# PCB_Design.net
KiCad netlist of a schematic drawn in Altium Designer
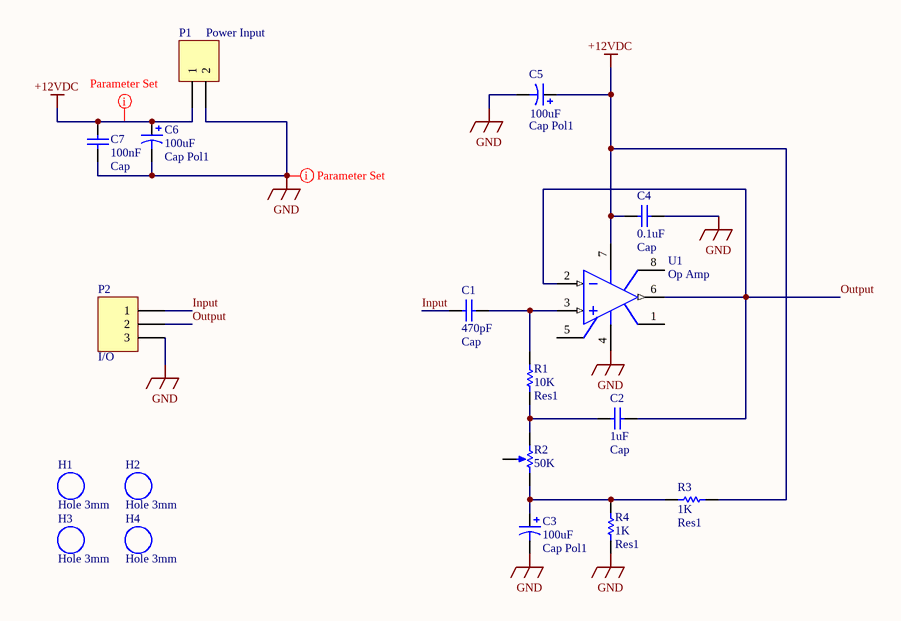
[diagram p0: PCB_Design.SchDoc]

(export (version "E")
  (design (tool "Eeschema 10.0.6"))
  (components
    (comp (ref "C1")
      (value "Cap")
      (footprint "RAD-0.3")
      (description "Capacitor")
      (fields (field (name "ALTIUM_VALUE") "470pF") (field (name "PUBLISHER") "Altium Limited"))
      (libsource (lib "Miscellaneous Devices") (part "Cap"))
    )
    (comp (ref "C2")
      (value "Cap")
      (footprint "RAD-0.3")
      (description "Capacitor")
      (fields (field (name "ALTIUM_VALUE") "1uF") (field (name "PUBLISHER") "Altium Limited"))
      (libsource (lib "Miscellaneous Devices") (part "Cap"))
    )
    (comp (ref "C3")
      (value "Cap Pol1")
      (footprint "RB7.6-15")
      (description "Polarized Capacitor (Radial)")
      (fields (field (name "ALTIUM_VALUE") "100uF") (field (name "PUBLISHER") "Altium Limited"))
      (libsource (lib "Miscellaneous Devices") (part "Cap Pol1"))
    )
    (comp (ref "C4")
      (value "Cap")
      (footprint "RAD-0.3")
      (description "Capacitor")
      (fields (field (name "ALTIUM_VALUE") "0.1uF") (field (name "PUBLISHER") "Altium Limited"))
      (libsource (lib "Miscellaneous Devices") (part "Cap"))
    )
    (comp (ref "C5")
      (value "Cap Pol1")
      (footprint "RB7.6-15")
      (description "Polarized Capacitor (Radial)")
      (fields (field (name "ALTIUM_VALUE") "100uF") (field (name "PUBLISHER") "Altium Limited"))
      (libsource (lib "Miscellaneous Devices") (part "Cap Pol1"))
    )
    (comp (ref "C6")
      (value "Cap Pol1")
      (footprint "RB7.6-15")
      (description "Polarized Capacitor (Radial)")
      (fields (field (name "ALTIUM_VALUE") "100uF") (field (name "PUBLISHER") "Altium Limited"))
      (libsource (lib "Miscellaneous Devices") (part "Cap Pol1"))
    )
    (comp (ref "C7")
      (value "Cap")
      (footprint "RAD-0.3")
      (description "Capacitor")
      (fields (field (name "ALTIUM_VALUE") "100nF") (field (name "PUBLISHER") "Altium Limited"))
      (libsource (lib "Miscellaneous Devices") (part "Cap"))
    )
    (comp (ref "H1")
      (value "Hole 3mm")
      (footprint "Hole 3mm")
      (libsource (lib "ECE Lib 22") (part "Hole 3mm"))
    )
    (comp (ref "H2")
      (value "Hole 3mm")
      (footprint "Hole 3mm")
      (libsource (lib "ECE Lib 22") (part "Hole 3mm"))
    )
    (comp (ref "H3")
      (value "Hole 3mm")
      (footprint "Hole 3mm")
      (libsource (lib "ECE Lib 22") (part "Hole 3mm"))
    )
    (comp (ref "H4")
      (value "Hole 3mm")
      (footprint "Hole 3mm")
      (libsource (lib "ECE Lib 22") (part "Hole 3mm"))
    )
    (comp (ref "P1")
      (value "Power Input")
      (footprint "HDR1X2")
      (description "Header, 2-Pin")
      (fields (field (name "PUBLISHER") "Altium Limited"))
      (libsource (lib "Miscellaneous Connectors") (part "Header 2"))
    )
    (comp (ref "P2")
      (value "I/O")
      (footprint "HDR1X3")
      (description "Header, 3-Pin")
      (fields (field (name "PUBLISHER") "Altium Limited"))
      (libsource (lib "Miscellaneous Connectors") (part "Header 3"))
    )
    (comp (ref "R1")
      (value "Res1")
      (footprint "AXIAL-0.3")
      (description "Resistor")
      (fields (field (name "ALTIUM_VALUE") "10K") (field (name "PUBLISHER") "Altium Limited"))
      (libsource (lib "Miscellaneous Devices") (part "Res1"))
    )
    (comp (ref "R2")
      (value "50K")
      (footprint "POT inline wide")
      (description "Potentiometer")
      (fields (field (name "Comment") "RPot_1") (field (name "PUBLISHER") "Altium Limited"))
      (libsource (lib "ECE Lib 22") (part "RPot_3"))
    )
    (comp (ref "R3")
      (value "Res1")
      (footprint "AXIAL-0.3")
      (description "Resistor")
      (fields (field (name "ALTIUM_VALUE") "1K") (field (name "PUBLISHER") "Altium Limited"))
      (libsource (lib "Miscellaneous Devices") (part "Res1"))
    )
    (comp (ref "R4")
      (value "Res1")
      (footprint "AXIAL-0.3")
      (description "Resistor")
      (fields (field (name "ALTIUM_VALUE") "1K") (field (name "PUBLISHER") "Altium Limited"))
      (libsource (lib "Miscellaneous Devices") (part "Res1"))
    )
    (comp (ref "U1")
      (value "Op Amp")
      (footprint "DIP-8")
      (description "FET Operational Amplifier")
      (fields (field (name "PUBLISHER") "Altium Limited"))
      (libsource (lib "Miscellaneous Devices") (part "Op Amp"))
    )
  )
  (nets
    (net (code "1") (name "+12VDC") (class "Default")
      (node (ref "C4") (pin "1") (pinfunction "1_1") (pintype "passive"))
      (node (ref "C5") (pin "1") (pinfunction "1_1") (pintype "passive"))
      (node (ref "C6") (pin "1") (pinfunction "1_1") (pintype "passive"))
      (node (ref "C7") (pin "2") (pinfunction "2_2") (pintype "passive"))
      (node (ref "P1") (pin "1") (pinfunction "1_1") (pintype "passive"))
      (node (ref "R3") (pin "1") (pinfunction "1_1") (pintype "passive"))
      (node (ref "U1") (pin "7") (pinfunction "V+_7") (pintype "power_in"))
    )
    (net (code "2") (name "/Input") (class "Default")
      (node (ref "C1") (pin "1") (pinfunction "1_1") (pintype "passive"))
      (node (ref "P2") (pin "1") (pinfunction "1_1") (pintype "passive"))
    )
    (net (code "3") (name "/Output") (class "Default")
      (node (ref "C2") (pin "2") (pinfunction "2_2") (pintype "passive"))
      (node (ref "P2") (pin "2") (pinfunction "2_2") (pintype "passive"))
      (node (ref "U1") (pin "2") (pinfunction "IN-_2") (pintype "input"))
      (node (ref "U1") (pin "6") (pinfunction "OUT_6") (pintype "output"))
    )
    (net (code "4") (name "GND") (class "Default")
      (node (ref "C3") (pin "2") (pinfunction "2_2") (pintype "passive"))
      (node (ref "C4") (pin "2") (pinfunction "2_2") (pintype "passive"))
      (node (ref "C5") (pin "2") (pinfunction "2_2") (pintype "passive"))
      (node (ref "C6") (pin "2") (pinfunction "2_2") (pintype "passive"))
      (node (ref "C7") (pin "1") (pinfunction "1_1") (pintype "passive"))
      (node (ref "P1") (pin "2") (pinfunction "2_2") (pintype "passive"))
      (node (ref "P2") (pin "3") (pinfunction "3_3") (pintype "passive"))
      (node (ref "R4") (pin "1") (pinfunction "1_1") (pintype "passive"))
      (node (ref "U1") (pin "4") (pinfunction "V-_4") (pintype "power_in"))
    )
    (net (code "5") (name "Net-(R2-BOT)") (class "Default")
      (node (ref "C3") (pin "1") (pinfunction "1_1") (pintype "passive"))
      (node (ref "R2") (pin "3") (pinfunction "BOT_3") (pintype "passive"))
      (node (ref "R3") (pin "2") (pinfunction "2_2") (pintype "passive"))
      (node (ref "R4") (pin "2") (pinfunction "2_2") (pintype "passive"))
    )
    (net (code "6") (name "Net-(R2-TOP)") (class "Default")
      (node (ref "C2") (pin "1") (pinfunction "1_1") (pintype "passive"))
      (node (ref "R1") (pin "1") (pinfunction "1_1") (pintype "passive"))
      (node (ref "R2") (pin "1") (pinfunction "TOP_1") (pintype "passive"))
    )
    (net (code "7") (name "Net-(U1-IN+)") (class "Default")
      (node (ref "C1") (pin "2") (pinfunction "2_2") (pintype "passive"))
      (node (ref "R1") (pin "2") (pinfunction "2_2") (pintype "passive"))
      (node (ref "U1") (pin "3") (pinfunction "IN+_3") (pintype "input"))
    )
    (net (code "8") (name "unconnected-(R2-TAP-Pad2)") (class "Default")
      (node (ref "R2") (pin "2") (pinfunction "TAP_2") (pintype "passive"))
    )
    (net (code "9") (name "unconnected-(U1-OS_NUL-Pad1)") (class "Default")
      (node (ref "U1") (pin "1") (pinfunction "OS_NUL_1") (pintype "passive"))
    )
    (net (code "10") (name "unconnected-(U1-OS_NUL-Pad5)") (class "Default")
      (node (ref "U1") (pin "5") (pinfunction "OS_NUL_5") (pintype "passive"))
    )
    (net (code "11") (name "unconnected-(U1-TAB-Pad8)") (class "Default")
      (node (ref "U1") (pin "8") (pinfunction "TAB_8") (pintype "passive"))
    )
  )
)
